# arrayboard_r1.net
KiCad netlist of a schematic drawn in EAGLE
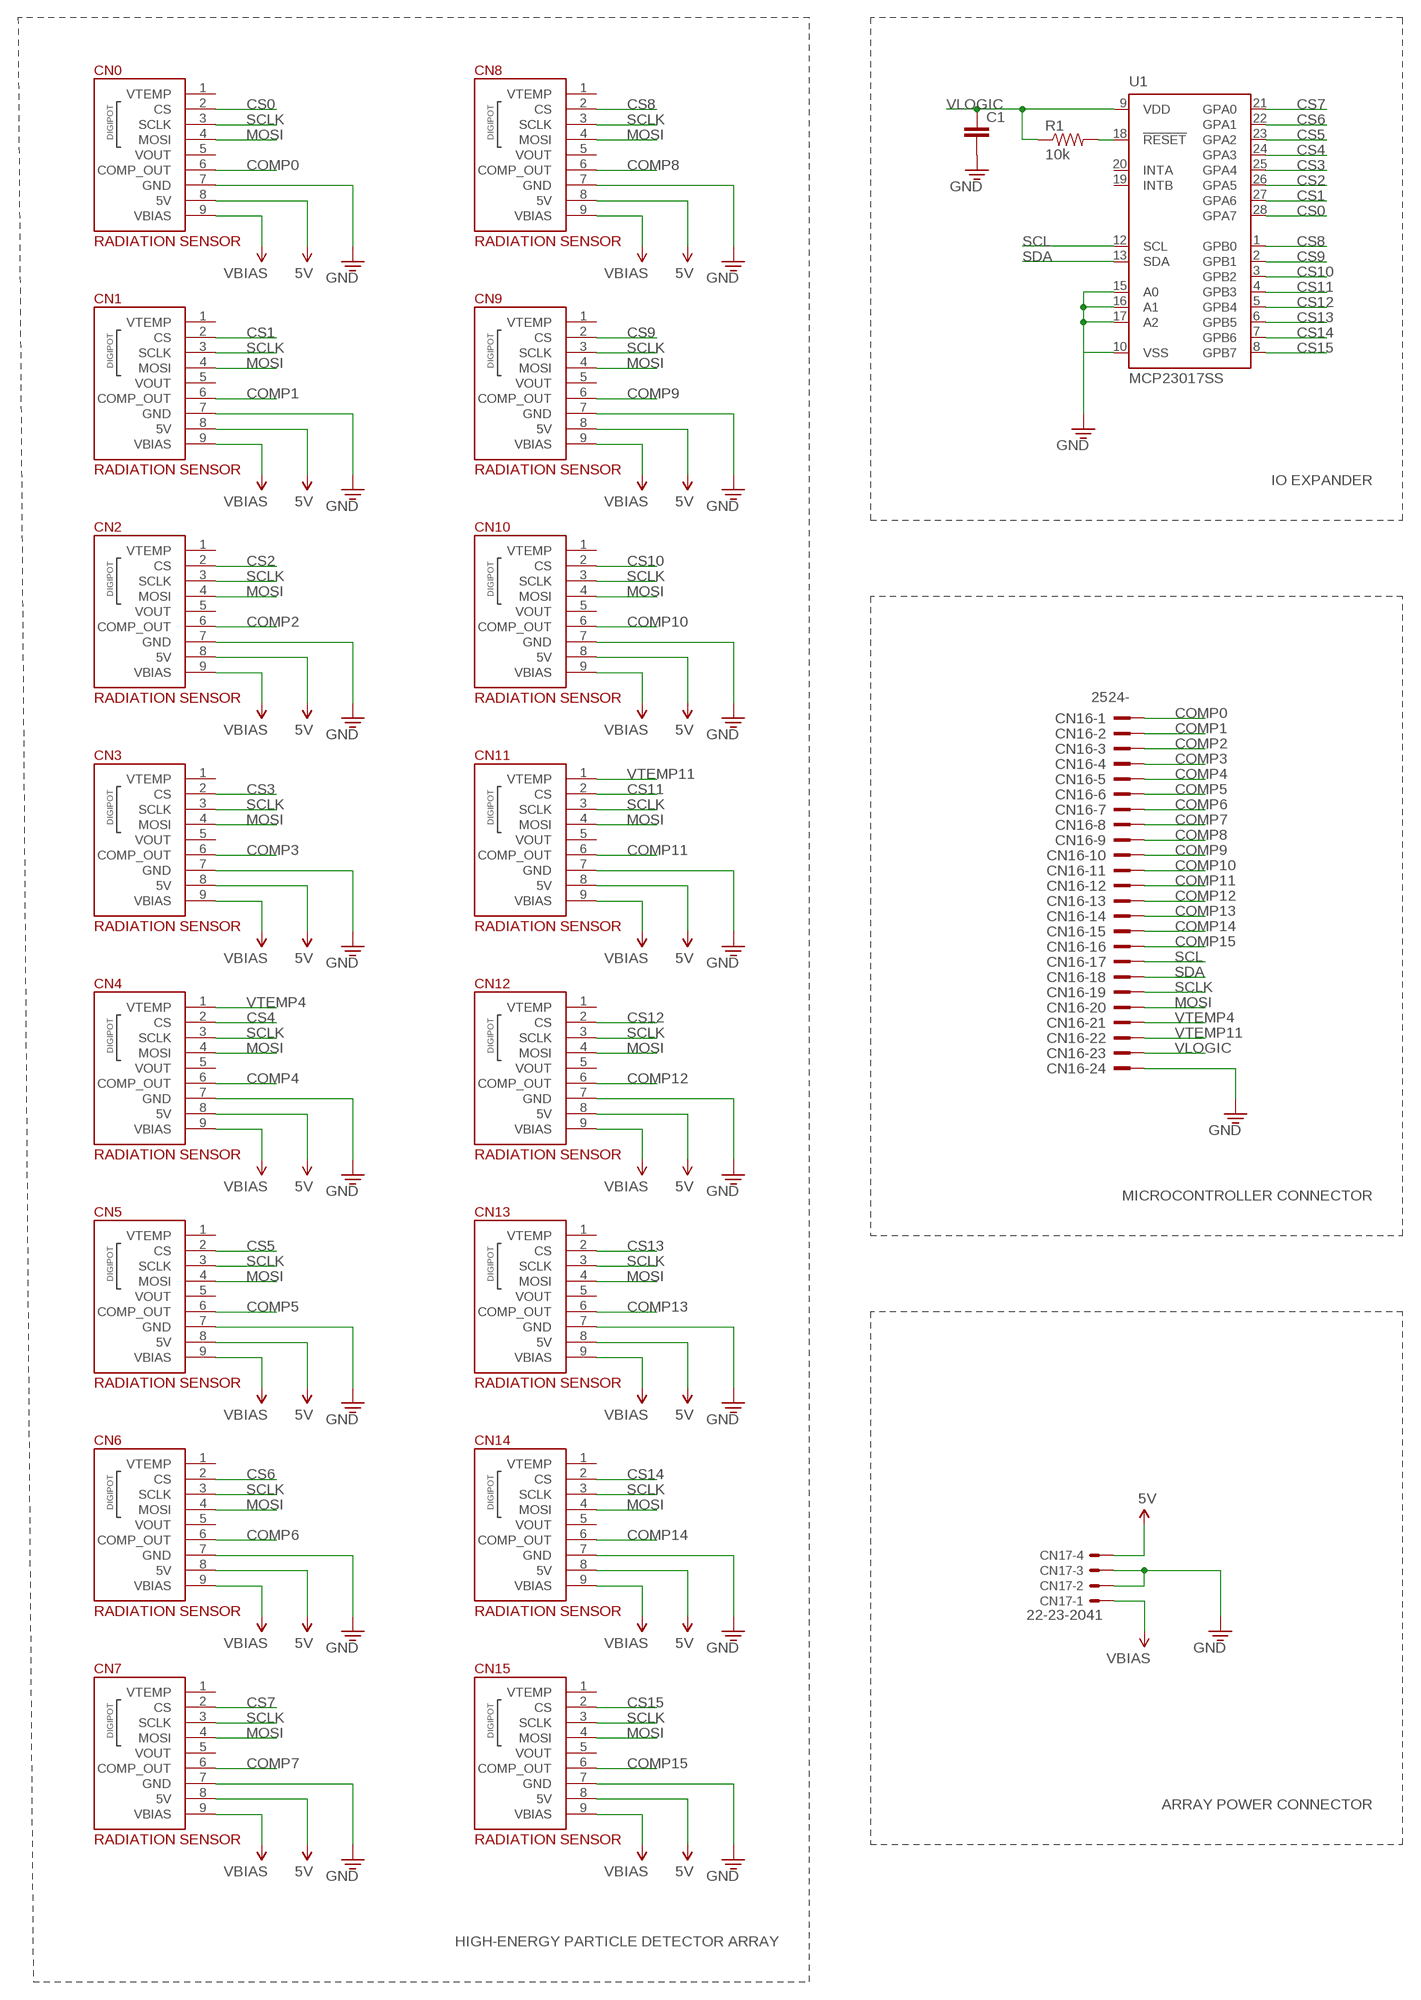
[diagram p0: schematic, sheet 1]

(export (version "E")
  (design (tool "Eeschema 10.0.6"))
  (components
    (comp (ref "C1")
      (value "CAP0603")
      (footprint "eagle-import:0603")
      (libsource (lib "eagle-import") (part "CAP0603"))
    )
    (comp (ref "CN0")
      (value "RADIATION-SENSOR-REV1")
      (footprint "eagle-import:RADIATION-SENSOR-REV1")
      (libsource (lib "eagle-import") (part "RADIATION-SENSOR-REV1"))
    )
    (comp (ref "CN1")
      (value "RADIATION-SENSOR-REV1")
      (footprint "eagle-import:RADIATION-SENSOR-REV1")
      (libsource (lib "eagle-import") (part "RADIATION-SENSOR-REV1"))
    )
    (comp (ref "CN2")
      (value "RADIATION-SENSOR-REV1")
      (footprint "eagle-import:RADIATION-SENSOR-REV1")
      (libsource (lib "eagle-import") (part "RADIATION-SENSOR-REV1"))
    )
    (comp (ref "CN3")
      (value "RADIATION-SENSOR-REV1")
      (footprint "eagle-import:RADIATION-SENSOR-REV1")
      (libsource (lib "eagle-import") (part "RADIATION-SENSOR-REV1"))
    )
    (comp (ref "CN4")
      (value "RADIATION-SENSOR-REV1")
      (footprint "eagle-import:RADIATION-SENSOR-REV1")
      (libsource (lib "eagle-import") (part "RADIATION-SENSOR-REV1"))
    )
    (comp (ref "CN5")
      (value "RADIATION-SENSOR-REV1")
      (footprint "eagle-import:RADIATION-SENSOR-REV1")
      (libsource (lib "eagle-import") (part "RADIATION-SENSOR-REV1"))
    )
    (comp (ref "CN6")
      (value "RADIATION-SENSOR-REV1")
      (footprint "eagle-import:RADIATION-SENSOR-REV1")
      (libsource (lib "eagle-import") (part "RADIATION-SENSOR-REV1"))
    )
    (comp (ref "CN7")
      (value "RADIATION-SENSOR-REV1")
      (footprint "eagle-import:RADIATION-SENSOR-REV1")
      (libsource (lib "eagle-import") (part "RADIATION-SENSOR-REV1"))
    )
    (comp (ref "CN8")
      (value "RADIATION-SENSOR-REV1")
      (footprint "eagle-import:RADIATION-SENSOR-REV1")
      (libsource (lib "eagle-import") (part "RADIATION-SENSOR-REV1"))
    )
    (comp (ref "CN9")
      (value "RADIATION-SENSOR-REV1")
      (footprint "eagle-import:RADIATION-SENSOR-REV1")
      (libsource (lib "eagle-import") (part "RADIATION-SENSOR-REV1"))
    )
    (comp (ref "CN10")
      (value "RADIATION-SENSOR-REV1")
      (footprint "eagle-import:RADIATION-SENSOR-REV1")
      (libsource (lib "eagle-import") (part "RADIATION-SENSOR-REV1"))
    )
    (comp (ref "CN11")
      (value "RADIATION-SENSOR-REV1")
      (footprint "eagle-import:RADIATION-SENSOR-REV1")
      (libsource (lib "eagle-import") (part "RADIATION-SENSOR-REV1"))
    )
    (comp (ref "CN12")
      (value "RADIATION-SENSOR-REV1")
      (footprint "eagle-import:RADIATION-SENSOR-REV1")
      (libsource (lib "eagle-import") (part "RADIATION-SENSOR-REV1"))
    )
    (comp (ref "CN13")
      (value "RADIATION-SENSOR-REV1")
      (footprint "eagle-import:RADIATION-SENSOR-REV1")
      (libsource (lib "eagle-import") (part "RADIATION-SENSOR-REV1"))
    )
    (comp (ref "CN14")
      (value "RADIATION-SENSOR-REV1")
      (footprint "eagle-import:RADIATION-SENSOR-REV1")
      (libsource (lib "eagle-import") (part "RADIATION-SENSOR-REV1"))
    )
    (comp (ref "CN15")
      (value "RADIATION-SENSOR-REV1")
      (footprint "eagle-import:RADIATION-SENSOR-REV1")
      (libsource (lib "eagle-import") (part "RADIATION-SENSOR-REV1"))
    )
    (comp (ref "CN16")
      (value "2524-")
      (footprint "eagle-import:PAK100_2500-24")
      (libsource (lib "eagle-import") (part "2524-"))
    )
    (comp (ref "CN17")
      (value "22-23-2041")
      (footprint "eagle-import:22-23-2041")
      (fields (field (name "MF") "MOLEX"))
      (libsource (lib "eagle-import") (part "22-23-2041"))
    )
    (comp (ref "R1")
      (value "10k")
      (footprint "eagle-import:0603")
      (libsource (lib "eagle-import") (part "RESISTOR0603"))
    )
    (comp (ref "U1")
      (value "MCP23017SS")
      (footprint "eagle-import:SSOP28")
      (libsource (lib "eagle-import") (part "MCP23017SS"))
    )
  )
  (nets
    (net (code "1") (name "/COMP0") (class "Default")
      (node (ref "CN0") (pin "6") (pinfunction "COMP_OUT_6") (pintype "bidirectional"))
      (node (ref "CN16") (pin "1") (pinfunction "KL_1") (pintype "passive"))
    )
    (net (code "2") (name "/COMP1") (class "Default")
      (node (ref "CN1") (pin "6") (pinfunction "COMP_OUT_6") (pintype "bidirectional"))
      (node (ref "CN16") (pin "2") (pinfunction "KL_2") (pintype "passive"))
    )
    (net (code "3") (name "/COMP2") (class "Default")
      (node (ref "CN16") (pin "3") (pinfunction "KL_3") (pintype "passive"))
      (node (ref "CN2") (pin "6") (pinfunction "COMP_OUT_6") (pintype "bidirectional"))
    )
    (net (code "4") (name "/COMP3") (class "Default")
      (node (ref "CN16") (pin "4") (pinfunction "KL_4") (pintype "passive"))
      (node (ref "CN3") (pin "6") (pinfunction "COMP_OUT_6") (pintype "bidirectional"))
    )
    (net (code "5") (name "/COMP4") (class "Default")
      (node (ref "CN16") (pin "5") (pinfunction "KL_5") (pintype "passive"))
      (node (ref "CN4") (pin "6") (pinfunction "COMP_OUT_6") (pintype "bidirectional"))
    )
    (net (code "6") (name "/COMP5") (class "Default")
      (node (ref "CN16") (pin "6") (pinfunction "KL_6") (pintype "passive"))
      (node (ref "CN5") (pin "6") (pinfunction "COMP_OUT_6") (pintype "bidirectional"))
    )
    (net (code "7") (name "/COMP6") (class "Default")
      (node (ref "CN16") (pin "7") (pinfunction "KL_7") (pintype "passive"))
      (node (ref "CN6") (pin "6") (pinfunction "COMP_OUT_6") (pintype "bidirectional"))
    )
    (net (code "8") (name "/COMP7") (class "Default")
      (node (ref "CN16") (pin "8") (pinfunction "KL_8") (pintype "passive"))
      (node (ref "CN7") (pin "6") (pinfunction "COMP_OUT_6") (pintype "bidirectional"))
    )
    (net (code "9") (name "/COMP8") (class "Default")
      (node (ref "CN16") (pin "9") (pinfunction "KL_9") (pintype "passive"))
      (node (ref "CN8") (pin "6") (pinfunction "COMP_OUT_6") (pintype "bidirectional"))
    )
    (net (code "10") (name "/COMP9") (class "Default")
      (node (ref "CN16") (pin "10") (pinfunction "KL_10") (pintype "passive"))
      (node (ref "CN9") (pin "6") (pinfunction "COMP_OUT_6") (pintype "bidirectional"))
    )
    (net (code "11") (name "/COMP10") (class "Default")
      (node (ref "CN10") (pin "6") (pinfunction "COMP_OUT_6") (pintype "bidirectional"))
      (node (ref "CN16") (pin "11") (pinfunction "KL_11") (pintype "passive"))
    )
    (net (code "12") (name "/COMP11") (class "Default")
      (node (ref "CN11") (pin "6") (pinfunction "COMP_OUT_6") (pintype "bidirectional"))
      (node (ref "CN16") (pin "12") (pinfunction "KL_12") (pintype "passive"))
    )
    (net (code "13") (name "/COMP12") (class "Default")
      (node (ref "CN12") (pin "6") (pinfunction "COMP_OUT_6") (pintype "bidirectional"))
      (node (ref "CN16") (pin "13") (pinfunction "KL_13") (pintype "passive"))
    )
    (net (code "14") (name "/COMP13") (class "Default")
      (node (ref "CN13") (pin "6") (pinfunction "COMP_OUT_6") (pintype "bidirectional"))
      (node (ref "CN16") (pin "14") (pinfunction "KL_14") (pintype "passive"))
    )
    (net (code "15") (name "/COMP14") (class "Default")
      (node (ref "CN14") (pin "6") (pinfunction "COMP_OUT_6") (pintype "bidirectional"))
      (node (ref "CN16") (pin "15") (pinfunction "KL_15") (pintype "passive"))
    )
    (net (code "16") (name "/COMP15") (class "Default")
      (node (ref "CN15") (pin "6") (pinfunction "COMP_OUT_6") (pintype "bidirectional"))
      (node (ref "CN16") (pin "16") (pinfunction "KL_16") (pintype "passive"))
    )
    (net (code "17") (name "/CS0") (class "Default")
      (node (ref "CN0") (pin "2") (pinfunction "CS_2") (pintype "bidirectional"))
      (node (ref "U1") (pin "28") (pinfunction "GPA7_28") (pintype "bidirectional"))
    )
    (net (code "18") (name "/CS1") (class "Default")
      (node (ref "CN1") (pin "2") (pinfunction "CS_2") (pintype "bidirectional"))
      (node (ref "U1") (pin "27") (pinfunction "GPA6_27") (pintype "bidirectional"))
    )
    (net (code "19") (name "/CS2") (class "Default")
      (node (ref "CN2") (pin "2") (pinfunction "CS_2") (pintype "bidirectional"))
      (node (ref "U1") (pin "26") (pinfunction "GPA5_26") (pintype "bidirectional"))
    )
    (net (code "20") (name "/CS3") (class "Default")
      (node (ref "CN3") (pin "2") (pinfunction "CS_2") (pintype "bidirectional"))
      (node (ref "U1") (pin "25") (pinfunction "GPA4_25") (pintype "bidirectional"))
    )
    (net (code "21") (name "/CS4") (class "Default")
      (node (ref "CN4") (pin "2") (pinfunction "CS_2") (pintype "bidirectional"))
      (node (ref "U1") (pin "24") (pinfunction "GPA3_24") (pintype "bidirectional"))
    )
    (net (code "22") (name "/CS5") (class "Default")
      (node (ref "CN5") (pin "2") (pinfunction "CS_2") (pintype "bidirectional"))
      (node (ref "U1") (pin "23") (pinfunction "GPA2_23") (pintype "bidirectional"))
    )
    (net (code "23") (name "/CS6") (class "Default")
      (node (ref "CN6") (pin "2") (pinfunction "CS_2") (pintype "bidirectional"))
      (node (ref "U1") (pin "22") (pinfunction "GPA1_22") (pintype "bidirectional"))
    )
    (net (code "24") (name "/CS7") (class "Default")
      (node (ref "CN7") (pin "2") (pinfunction "CS_2") (pintype "bidirectional"))
      (node (ref "U1") (pin "21") (pinfunction "GPA0_21") (pintype "bidirectional"))
    )
    (net (code "25") (name "/CS8") (class "Default")
      (node (ref "CN8") (pin "2") (pinfunction "CS_2") (pintype "bidirectional"))
      (node (ref "U1") (pin "1") (pinfunction "GPB0_1") (pintype "bidirectional"))
    )
    (net (code "26") (name "/CS9") (class "Default")
      (node (ref "CN9") (pin "2") (pinfunction "CS_2") (pintype "bidirectional"))
      (node (ref "U1") (pin "2") (pinfunction "GPB1_2") (pintype "bidirectional"))
    )
    (net (code "27") (name "/CS10") (class "Default")
      (node (ref "CN10") (pin "2") (pinfunction "CS_2") (pintype "bidirectional"))
      (node (ref "U1") (pin "3") (pinfunction "GPB2_3") (pintype "bidirectional"))
    )
    (net (code "28") (name "/CS11") (class "Default")
      (node (ref "CN11") (pin "2") (pinfunction "CS_2") (pintype "bidirectional"))
      (node (ref "U1") (pin "4") (pinfunction "GPB3_4") (pintype "bidirectional"))
    )
    (net (code "29") (name "/CS12") (class "Default")
      (node (ref "CN12") (pin "2") (pinfunction "CS_2") (pintype "bidirectional"))
      (node (ref "U1") (pin "5") (pinfunction "GPB4_5") (pintype "bidirectional"))
    )
    (net (code "30") (name "/CS13") (class "Default")
      (node (ref "CN13") (pin "2") (pinfunction "CS_2") (pintype "bidirectional"))
      (node (ref "U1") (pin "6") (pinfunction "GPB5_6") (pintype "bidirectional"))
    )
    (net (code "31") (name "/CS14") (class "Default")
      (node (ref "CN14") (pin "2") (pinfunction "CS_2") (pintype "bidirectional"))
      (node (ref "U1") (pin "7") (pinfunction "GPB6_7") (pintype "bidirectional"))
    )
    (net (code "32") (name "/CS15") (class "Default")
      (node (ref "CN15") (pin "2") (pinfunction "CS_2") (pintype "bidirectional"))
      (node (ref "U1") (pin "8") (pinfunction "GPB7_8") (pintype "bidirectional"))
    )
    (net (code "33") (name "/MOSI") (class "Default")
      (node (ref "CN0") (pin "4") (pinfunction "MOSI_4") (pintype "bidirectional"))
      (node (ref "CN1") (pin "4") (pinfunction "MOSI_4") (pintype "bidirectional"))
      (node (ref "CN10") (pin "4") (pinfunction "MOSI_4") (pintype "bidirectional"))
      (node (ref "CN11") (pin "4") (pinfunction "MOSI_4") (pintype "bidirectional"))
      (node (ref "CN12") (pin "4") (pinfunction "MOSI_4") (pintype "bidirectional"))
      (node (ref "CN13") (pin "4") (pinfunction "MOSI_4") (pintype "bidirectional"))
      (node (ref "CN14") (pin "4") (pinfunction "MOSI_4") (pintype "bidirectional"))
      (node (ref "CN15") (pin "4") (pinfunction "MOSI_4") (pintype "bidirectional"))
      (node (ref "CN16") (pin "20") (pinfunction "KL_20") (pintype "passive"))
      (node (ref "CN2") (pin "4") (pinfunction "MOSI_4") (pintype "bidirectional"))
      (node (ref "CN3") (pin "4") (pinfunction "MOSI_4") (pintype "bidirectional"))
      (node (ref "CN4") (pin "4") (pinfunction "MOSI_4") (pintype "bidirectional"))
      (node (ref "CN5") (pin "4") (pinfunction "MOSI_4") (pintype "bidirectional"))
      (node (ref "CN6") (pin "4") (pinfunction "MOSI_4") (pintype "bidirectional"))
      (node (ref "CN7") (pin "4") (pinfunction "MOSI_4") (pintype "bidirectional"))
      (node (ref "CN8") (pin "4") (pinfunction "MOSI_4") (pintype "bidirectional"))
      (node (ref "CN9") (pin "4") (pinfunction "MOSI_4") (pintype "bidirectional"))
    )
    (net (code "34") (name "/SCL") (class "Default")
      (node (ref "CN16") (pin "17") (pinfunction "KL_17") (pintype "passive"))
      (node (ref "U1") (pin "12") (pinfunction "SCL_12") (pintype "input"))
    )
    (net (code "35") (name "/SCLK") (class "Default")
      (node (ref "CN0") (pin "3") (pinfunction "SCLK_3") (pintype "bidirectional"))
      (node (ref "CN1") (pin "3") (pinfunction "SCLK_3") (pintype "bidirectional"))
      (node (ref "CN10") (pin "3") (pinfunction "SCLK_3") (pintype "bidirectional"))
      (node (ref "CN11") (pin "3") (pinfunction "SCLK_3") (pintype "bidirectional"))
      (node (ref "CN12") (pin "3") (pinfunction "SCLK_3") (pintype "bidirectional"))
      (node (ref "CN13") (pin "3") (pinfunction "SCLK_3") (pintype "bidirectional"))
      (node (ref "CN14") (pin "3") (pinfunction "SCLK_3") (pintype "bidirectional"))
      (node (ref "CN15") (pin "3") (pinfunction "SCLK_3") (pintype "bidirectional"))
      (node (ref "CN16") (pin "19") (pinfunction "KL_19") (pintype "passive"))
      (node (ref "CN2") (pin "3") (pinfunction "SCLK_3") (pintype "bidirectional"))
      (node (ref "CN3") (pin "3") (pinfunction "SCLK_3") (pintype "bidirectional"))
      (node (ref "CN4") (pin "3") (pinfunction "SCLK_3") (pintype "bidirectional"))
      (node (ref "CN5") (pin "3") (pinfunction "SCLK_3") (pintype "bidirectional"))
      (node (ref "CN6") (pin "3") (pinfunction "SCLK_3") (pintype "bidirectional"))
      (node (ref "CN7") (pin "3") (pinfunction "SCLK_3") (pintype "bidirectional"))
      (node (ref "CN8") (pin "3") (pinfunction "SCLK_3") (pintype "bidirectional"))
      (node (ref "CN9") (pin "3") (pinfunction "SCLK_3") (pintype "bidirectional"))
    )
    (net (code "36") (name "/SDA") (class "Default")
      (node (ref "CN16") (pin "18") (pinfunction "KL_18") (pintype "passive"))
      (node (ref "U1") (pin "13") (pinfunction "SDA_13") (pintype "bidirectional"))
    )
    (net (code "37") (name "/VLOGIC") (class "Default")
      (node (ref "C1") (pin "1") (pinfunction "1_1") (pintype "passive"))
      (node (ref "CN16") (pin "23") (pinfunction "KL_23") (pintype "passive"))
      (node (ref "R1") (pin "1") (pinfunction "1_1") (pintype "passive"))
      (node (ref "U1") (pin "9") (pinfunction "VDD_9") (pintype "power_in"))
    )
    (net (code "38") (name "/VTEMP4") (class "Default")
      (node (ref "CN16") (pin "21") (pinfunction "KL_21") (pintype "passive"))
      (node (ref "CN4") (pin "1") (pinfunction "VTEMP_1") (pintype "bidirectional"))
    )
    (net (code "39") (name "/VTEMP11") (class "Default")
      (node (ref "CN11") (pin "1") (pinfunction "VTEMP_1") (pintype "bidirectional"))
      (node (ref "CN16") (pin "22") (pinfunction "KL_22") (pintype "passive"))
    )
    (net (code "40") (name "5V") (class "Default")
      (node (ref "CN0") (pin "8") (pinfunction "5V_8") (pintype "bidirectional"))
      (node (ref "CN1") (pin "8") (pinfunction "5V_8") (pintype "bidirectional"))
      (node (ref "CN10") (pin "8") (pinfunction "5V_8") (pintype "bidirectional"))
      (node (ref "CN11") (pin "8") (pinfunction "5V_8") (pintype "bidirectional"))
      (node (ref "CN12") (pin "8") (pinfunction "5V_8") (pintype "bidirectional"))
      (node (ref "CN13") (pin "8") (pinfunction "5V_8") (pintype "bidirectional"))
      (node (ref "CN14") (pin "8") (pinfunction "5V_8") (pintype "bidirectional"))
      (node (ref "CN15") (pin "8") (pinfunction "5V_8") (pintype "bidirectional"))
      (node (ref "CN17") (pin "4") (pinfunction "S_4") (pintype "passive"))
      (node (ref "CN2") (pin "8") (pinfunction "5V_8") (pintype "bidirectional"))
      (node (ref "CN3") (pin "8") (pinfunction "5V_8") (pintype "bidirectional"))
      (node (ref "CN4") (pin "8") (pinfunction "5V_8") (pintype "bidirectional"))
      (node (ref "CN5") (pin "8") (pinfunction "5V_8") (pintype "bidirectional"))
      (node (ref "CN6") (pin "8") (pinfunction "5V_8") (pintype "bidirectional"))
      (node (ref "CN7") (pin "8") (pinfunction "5V_8") (pintype "bidirectional"))
      (node (ref "CN8") (pin "8") (pinfunction "5V_8") (pintype "bidirectional"))
      (node (ref "CN9") (pin "8") (pinfunction "5V_8") (pintype "bidirectional"))
    )
    (net (code "41") (name "GND") (class "Default")
      (node (ref "C1") (pin "2") (pinfunction "2_2") (pintype "passive"))
      (node (ref "CN0") (pin "7") (pinfunction "GND_7") (pintype "bidirectional"))
      (node (ref "CN1") (pin "7") (pinfunction "GND_7") (pintype "bidirectional"))
      (node (ref "CN10") (pin "7") (pinfunction "GND_7") (pintype "bidirectional"))
      (node (ref "CN11") (pin "7") (pinfunction "GND_7") (pintype "bidirectional"))
      (node (ref "CN12") (pin "7") (pinfunction "GND_7") (pintype "bidirectional"))
      (node (ref "CN13") (pin "7") (pinfunction "GND_7") (pintype "bidirectional"))
      (node (ref "CN14") (pin "7") (pinfunction "GND_7") (pintype "bidirectional"))
      (node (ref "CN15") (pin "7") (pinfunction "GND_7") (pintype "bidirectional"))
      (node (ref "CN16") (pin "24") (pinfunction "KL_24") (pintype "passive"))
      (node (ref "CN17") (pin "2") (pinfunction "S_2") (pintype "passive"))
      (node (ref "CN17") (pin "3") (pinfunction "S_3") (pintype "passive"))
      (node (ref "CN2") (pin "7") (pinfunction "GND_7") (pintype "bidirectional"))
      (node (ref "CN3") (pin "7") (pinfunction "GND_7") (pintype "bidirectional"))
      (node (ref "CN4") (pin "7") (pinfunction "GND_7") (pintype "bidirectional"))
      (node (ref "CN5") (pin "7") (pinfunction "GND_7") (pintype "bidirectional"))
      (node (ref "CN6") (pin "7") (pinfunction "GND_7") (pintype "bidirectional"))
      (node (ref "CN7") (pin "7") (pinfunction "GND_7") (pintype "bidirectional"))
      (node (ref "CN8") (pin "7") (pinfunction "GND_7") (pintype "bidirectional"))
      (node (ref "CN9") (pin "7") (pinfunction "GND_7") (pintype "bidirectional"))
      (node (ref "U1") (pin "10") (pinfunction "VSS_10") (pintype "power_in"))
      (node (ref "U1") (pin "15") (pinfunction "A0_15") (pintype "input"))
      (node (ref "U1") (pin "16") (pinfunction "A1_16") (pintype "input"))
      (node (ref "U1") (pin "17") (pinfunction "A2_17") (pintype "input"))
    )
    (net (code "42") (name "Net-(U1-~{RESET})") (class "Default")
      (node (ref "R1") (pin "2") (pinfunction "2_2") (pintype "passive"))
      (node (ref "U1") (pin "18") (pinfunction "~{RESET}_18") (pintype "input"))
    )
    (net (code "43") (name "VBIAS") (class "Default")
      (node (ref "CN0") (pin "9") (pinfunction "VBIAS_9") (pintype "bidirectional"))
      (node (ref "CN1") (pin "9") (pinfunction "VBIAS_9") (pintype "bidirectional"))
      (node (ref "CN10") (pin "9") (pinfunction "VBIAS_9") (pintype "bidirectional"))
      (node (ref "CN11") (pin "9") (pinfunction "VBIAS_9") (pintype "bidirectional"))
      (node (ref "CN12") (pin "9") (pinfunction "VBIAS_9") (pintype "bidirectional"))
      (node (ref "CN13") (pin "9") (pinfunction "VBIAS_9") (pintype "bidirectional"))
      (node (ref "CN14") (pin "9") (pinfunction "VBIAS_9") (pintype "bidirectional"))
      (node (ref "CN15") (pin "9") (pinfunction "VBIAS_9") (pintype "bidirectional"))
      (node (ref "CN17") (pin "1") (pinfunction "S_1") (pintype "passive"))
      (node (ref "CN2") (pin "9") (pinfunction "VBIAS_9") (pintype "bidirectional"))
      (node (ref "CN3") (pin "9") (pinfunction "VBIAS_9") (pintype "bidirectional"))
      (node (ref "CN4") (pin "9") (pinfunction "VBIAS_9") (pintype "bidirectional"))
      (node (ref "CN5") (pin "9") (pinfunction "VBIAS_9") (pintype "bidirectional"))
      (node (ref "CN6") (pin "9") (pinfunction "VBIAS_9") (pintype "bidirectional"))
      (node (ref "CN7") (pin "9") (pinfunction "VBIAS_9") (pintype "bidirectional"))
      (node (ref "CN8") (pin "9") (pinfunction "VBIAS_9") (pintype "bidirectional"))
      (node (ref "CN9") (pin "9") (pinfunction "VBIAS_9") (pintype "bidirectional"))
    )
    (net (code "44") (name "unconnected-(CN0-VOUT-Pad5)") (class "Default")
      (node (ref "CN0") (pin "5") (pinfunction "VOUT_5") (pintype "bidirectional"))
    )
    (net (code "45") (name "unconnected-(CN0-VTEMP-Pad1)") (class "Default")
      (node (ref "CN0") (pin "1") (pinfunction "VTEMP_1") (pintype "bidirectional"))
    )
    (net (code "46") (name "unconnected-(CN1-VOUT-Pad5)") (class "Default")
      (node (ref "CN1") (pin "5") (pinfunction "VOUT_5") (pintype "bidirectional"))
    )
    (net (code "47") (name "unconnected-(CN1-VTEMP-Pad1)") (class "Default")
      (node (ref "CN1") (pin "1") (pinfunction "VTEMP_1") (pintype "bidirectional"))
    )
    (net (code "48") (name "unconnected-(CN2-VOUT-Pad5)") (class "Default")
      (node (ref "CN2") (pin "5") (pinfunction "VOUT_5") (pintype "bidirectional"))
    )
    (net (code "49") (name "unconnected-(CN2-VTEMP-Pad1)") (class "Default")
      (node (ref "CN2") (pin "1") (pinfunction "VTEMP_1") (pintype "bidirectional"))
    )
    (net (code "50") (name "unconnected-(CN3-VOUT-Pad5)") (class "Default")
      (node (ref "CN3") (pin "5") (pinfunction "VOUT_5") (pintype "bidirectional"))
    )
    (net (code "51") (name "unconnected-(CN3-VTEMP-Pad1)") (class "Default")
      (node (ref "CN3") (pin "1") (pinfunction "VTEMP_1") (pintype "bidirectional"))
    )
    (net (code "52") (name "unconnected-(CN4-VOUT-Pad5)") (class "Default")
      (node (ref "CN4") (pin "5") (pinfunction "VOUT_5") (pintype "bidirectional"))
    )
    (net (code "53") (name "unconnected-(CN5-VOUT-Pad5)") (class "Default")
      (node (ref "CN5") (pin "5") (pinfunction "VOUT_5") (pintype "bidirectional"))
    )
    (net (code "54") (name "unconnected-(CN5-VTEMP-Pad1)") (class "Default")
      (node (ref "CN5") (pin "1") (pinfunction "VTEMP_1") (pintype "bidirectional"))
    )
    (net (code "55") (name "unconnected-(CN6-VOUT-Pad5)") (class "Default")
      (node (ref "CN6") (pin "5") (pinfunction "VOUT_5") (pintype "bidirectional"))
    )
    (net (code "56") (name "unconnected-(CN6-VTEMP-Pad1)") (class "Default")
      (node (ref "CN6") (pin "1") (pinfunction "VTEMP_1") (pintype "bidirectional"))
    )
    (net (code "57") (name "unconnected-(CN7-VOUT-Pad5)") (class "Default")
      (node (ref "CN7") (pin "5") (pinfunction "VOUT_5") (pintype "bidirectional"))
    )
    (net (code "58") (name "unconnected-(CN7-VTEMP-Pad1)") (class "Default")
      (node (ref "CN7") (pin "1") (pinfunction "VTEMP_1") (pintype "bidirectional"))
    )
    (net (code "59") (name "unconnected-(CN8-VOUT-Pad5)") (class "Default")
      (node (ref "CN8") (pin "5") (pinfunction "VOUT_5") (pintype "bidirectional"))
    )
    (net (code "60") (name "unconnected-(CN8-VTEMP-Pad1)") (class "Default")
      (node (ref "CN8") (pin "1") (pinfunction "VTEMP_1") (pintype "bidirectional"))
    )
    (net (code "61") (name "unconnected-(CN9-VOUT-Pad5)") (class "Default")
      (node (ref "CN9") (pin "5") (pinfunction "VOUT_5") (pintype "bidirectional"))
    )
    (net (code "62") (name "unconnected-(CN9-VTEMP-Pad1)") (class "Default")
      (node (ref "CN9") (pin "1") (pinfunction "VTEMP_1") (pintype "bidirectional"))
    )
    (net (code "63") (name "unconnected-(CN10-VOUT-Pad5)") (class "Default")
      (node (ref "CN10") (pin "5") (pinfunction "VOUT_5") (pintype "bidirectional"))
    )
    (net (code "64") (name "unconnected-(CN10-VTEMP-Pad1)") (class "Default")
      (node (ref "CN10") (pin "1") (pinfunction "VTEMP_1") (pintype "bidirectional"))
    )
    (net (code "65") (name "unconnected-(CN11-VOUT-Pad5)") (class "Default")
      (node (ref "CN11") (pin "5") (pinfunction "VOUT_5") (pintype "bidirectional"))
    )
    (net (code "66") (name "unconnected-(CN12-VOUT-Pad5)") (class "Default")
      (node (ref "CN12") (pin "5") (pinfunction "VOUT_5") (pintype "bidirectional"))
    )
    (net (code "67") (name "unconnected-(CN12-VTEMP-Pad1)") (class "Default")
      (node (ref "CN12") (pin "1") (pinfunction "VTEMP_1") (pintype "bidirectional"))
    )
    (net (code "68") (name "unconnected-(CN13-VOUT-Pad5)") (class "Default")
      (node (ref "CN13") (pin "5") (pinfunction "VOUT_5") (pintype "bidirectional"))
    )
    (net (code "69") (name "unconnected-(CN13-VTEMP-Pad1)") (class "Default")
      (node (ref "CN13") (pin "1") (pinfunction "VTEMP_1") (pintype "bidirectional"))
    )
    (net (code "70") (name "unconnected-(CN14-VOUT-Pad5)") (class "Default")
      (node (ref "CN14") (pin "5") (pinfunction "VOUT_5") (pintype "bidirectional"))
    )
    (net (code "71") (name "unconnected-(CN14-VTEMP-Pad1)") (class "Default")
      (node (ref "CN14") (pin "1") (pinfunction "VTEMP_1") (pintype "bidirectional"))
    )
    (net (code "72") (name "unconnected-(CN15-VOUT-Pad5)") (class "Default")
      (node (ref "CN15") (pin "5") (pinfunction "VOUT_5") (pintype "bidirectional"))
    )
    (net (code "73") (name "unconnected-(CN15-VTEMP-Pad1)") (class "Default")
      (node (ref "CN15") (pin "1") (pinfunction "VTEMP_1") (pintype "bidirectional"))
    )
    (net (code "74") (name "unconnected-(U1-INTA-Pad20)") (class "Default")
      (node (ref "U1") (pin "20") (pinfunction "INTA_20") (pintype "output"))
    )
    (net (code "75") (name "unconnected-(U1-INTB-Pad19)") (class "Default")
      (node (ref "U1") (pin "19") (pinfunction "INTB_19") (pintype "output"))
    )
  )
)
